# Ctrl-CAN.net
KiCad netlist of a schematic drawn in Altium Designer
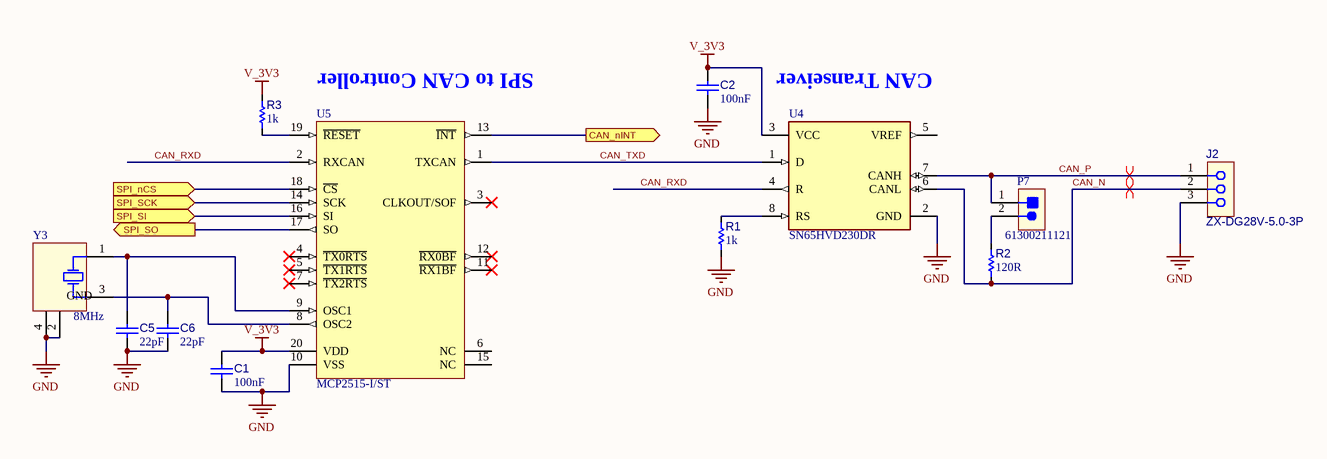
[diagram p0: Ctrl-CAN.SchDoc]

(export (version "E")
  (design (tool "Eeschema 10.0.6"))
  (components
    (comp (ref "C1")
      (value "100nF")
      (footprint "C_1005[0402]")
      (description "Capacitor type 1")
      (fields (field (name "TOLERANCE") "10%") (field (name "Comment") "CAP CER 100nF 50V 0402"))
      (libsource (lib "TEP-AltiumLib-Passives-RLC") (part "capacitor"))
    )
    (comp (ref "C2")
      (value "100nF")
      (footprint "C_1005[0402]")
      (description "Capacitor type 1")
      (fields (field (name "TOLERANCE") "10%") (field (name "Comment") "CAP CER 100nF 50V 0402"))
      (libsource (lib "TEP-AltiumLib-Passives-RLC") (part "capacitor"))
    )
    (comp (ref "C5")
      (value "22pF")
      (footprint "C_1005[0402]")
      (description "Capacitor type 1")
      (fields (field (name "TOLERANCE") "5%") (field (name "Comment") "CAP CER 22pF 50V COG 0402"))
      (libsource (lib "TEP-AltiumLib-Passives-RLC") (part "capacitor"))
    )
    (comp (ref "C6")
      (value "22pF")
      (footprint "C_1005[0402]")
      (description "Capacitor type 1")
      (fields (field (name "TOLERANCE") "5%") (field (name "Comment") "CAP CER 22pF 50V COG 0402"))
      (libsource (lib "TEP-AltiumLib-Passives-RLC") (part "capacitor"))
    )
    (comp (ref "J2")
      (value "ZX-DG28V-5.0-3P")
      (footprint "CONN_TERM_BLOCK_3POS_5mm_Model1")
      (description "CONN TERM BLOCK 3POS 5mm pitch")
      (libsource (lib "TEP-AltiumLib-Connectors") (part "CONN-5MM-3POS-TERM-BLOCK"))
    )
    (comp (ref "P7")
      (value "61300211121")
      (footprint "CONN_HDR_2POS_100MILS_TH")
      (description "CONN HEADER 2POS 100MIL")
      (libsource (lib "TEP-AltiumLib-Connectors") (part "CONN-100MIL-HDR-01X02"))
    )
    (comp (ref "R1")
      (value "1k")
      (footprint "R_1005[0402]")
      (description "Resistor type 1")
      (fields (field (name "TOLERANCE") "1%") (field (name "Comment") "Res 1k 1% 0402"))
      (libsource (lib "TEP-AltiumLib-Passives-RLC") (part "resistor"))
    )
    (comp (ref "R2")
      (value "120R")
      (footprint "R_3216[1206]")
      (description "Resistor type 1")
      (fields (field (name "TOLERANCE") "1%") (field (name "Comment") "Res 120R 1% 1206"))
      (libsource (lib "TEP-AltiumLib-Passives-RLC") (part "resistor"))
    )
    (comp (ref "R3")
      (value "1k")
      (footprint "R_1005[0402]")
      (description "Resistor type 1")
      (fields (field (name "TOLERANCE") "1%") (field (name "Comment") "Res 1k 1% 0402"))
      (libsource (lib "TEP-AltiumLib-Passives-RLC") (part "resistor"))
    )
    (comp (ref "U4")
      (value "SN65HVD230DR")
      (footprint "FP-D0008A-IPC_A")
      (description "IC TRANSCEIVER HALF 1/1 8SOIC")
      (libsource (lib "Altium Content Vault") (part "43b56812b1adf0e60a7acfb7c27ab91"))
    )
    (comp (ref "U5")
      (value "MCP2515-I/ST")
      (footprint "TSSOP-ST20_N")
      (description "Stand-Alone CAN Controller With SPI Interface, 20-Pin TSSOP, Industrial Temperature")
      (libsource (lib "Altium Content Vault") (part "COM-CAN-MCP2515-20"))
    )
    (comp (ref "Y3")
      (value "8MHz")
      (footprint "Y_32x25SMD4")
      (description "Crystal, 8MHz, 3.2 x 2.5 x 0.9 mm SMD")
      (fields (field (name "Comment") "XC32M4-8.000-F18LJDT"))
      (libsource (lib "SAP") (part "Y_XTAL25MHz"))
    )
  )
  (nets
    (net (code "1") (name "/CAN_N") (class "Default")
      (node (ref "J2") (pin "2") (pinfunction "2_2") (pintype "passive"))
      (node (ref "R2") (pin "1") (pinfunction "1_1") (pintype "passive"))
      (node (ref "U4") (pin "6") (pinfunction "CANL_6") (pintype "bidirectional"))
    )
    (net (code "2") (name "/CAN_P") (class "Default")
      (node (ref "J2") (pin "1") (pinfunction "1_1") (pintype "passive"))
      (node (ref "P7") (pin "1") (pinfunction "1_1") (pintype "passive"))
      (node (ref "U4") (pin "7") (pinfunction "CANH_7") (pintype "bidirectional"))
    )
    (net (code "3") (name "/CAN_RXD") (class "Default")
      (node (ref "U4") (pin "4") (pinfunction "R_4") (pintype "output"))
      (node (ref "U5") (pin "2") (pinfunction "RXCAN_2") (pintype "input"))
    )
    (net (code "4") (name "/CAN_TXD") (class "Default")
      (node (ref "U4") (pin "1") (pinfunction "D_1") (pintype "input"))
      (node (ref "U5") (pin "1") (pinfunction "TXCAN_1") (pintype "output"))
    )
    (net (code "5") (name "/CAN_nINT") (class "Default")
      (node (ref "U5") (pin "13") (pinfunction "~{INT}_13") (pintype "output"))
    )
    (net (code "6") (name "/SPI_SCK") (class "Default")
      (node (ref "U5") (pin "14") (pinfunction "SCK_14") (pintype "input"))
    )
    (net (code "7") (name "/SPI_SI") (class "Default")
      (node (ref "U5") (pin "16") (pinfunction "SI_16") (pintype "input"))
    )
    (net (code "8") (name "/SPI_SO") (class "Default")
      (node (ref "U5") (pin "17") (pinfunction "SO_17") (pintype "output"))
    )
    (net (code "9") (name "/SPI_nCS") (class "Default")
      (node (ref "U5") (pin "18") (pinfunction "~{CS}_18") (pintype "input"))
    )
    (net (code "10") (name "GND") (class "Default")
      (node (ref "C1") (pin "1") (pinfunction "1_1") (pintype "passive"))
      (node (ref "C2") (pin "1") (pinfunction "1_1") (pintype "passive"))
      (node (ref "C5") (pin "1") (pinfunction "1_1") (pintype "passive"))
      (node (ref "C6") (pin "1") (pinfunction "1_1") (pintype "passive"))
      (node (ref "J2") (pin "3") (pinfunction "3_3") (pintype "passive"))
      (node (ref "R1") (pin "1") (pinfunction "1_1") (pintype "passive"))
      (node (ref "U4") (pin "2") (pinfunction "GND_2") (pintype "power_in"))
      (node (ref "U5") (pin "10") (pinfunction "VSS_10") (pintype "power_in"))
      (node (ref "Y3") (pin "2") (pinfunction "GND_2") (pintype "power_in"))
      (node (ref "Y3") (pin "4") (pinfunction "GND_4") (pintype "power_in"))
    )
    (net (code "11") (name "Net-(P7-Pad2)") (class "Default")
      (node (ref "P7") (pin "2") (pinfunction "2_2") (pintype "passive"))
      (node (ref "R2") (pin "2") (pinfunction "2_2") (pintype "passive"))
    )
    (net (code "12") (name "Net-(U4-RS)") (class "Default")
      (node (ref "R1") (pin "2") (pinfunction "2_2") (pintype "passive"))
      (node (ref "U4") (pin "8") (pinfunction "RS_8") (pintype "input"))
    )
    (net (code "13") (name "Net-(U5-OSC1)") (class "Default")
      (node (ref "C5") (pin "2") (pinfunction "2_2") (pintype "passive"))
      (node (ref "U5") (pin "9") (pinfunction "OSC1_9") (pintype "input"))
      (node (ref "Y3") (pin "1") (pinfunction "XTAL_1") (pintype "passive"))
    )
    (net (code "14") (name "Net-(U5-OSC2)") (class "Default")
      (node (ref "C6") (pin "2") (pinfunction "2_2") (pintype "passive"))
      (node (ref "U5") (pin "8") (pinfunction "OSC2_8") (pintype "output"))
      (node (ref "Y3") (pin "3") (pinfunction "XTAL_3") (pintype "passive"))
    )
    (net (code "15") (name "Net-(U5-~{RESET})") (class "Default")
      (node (ref "R3") (pin "1") (pinfunction "1_1") (pintype "passive"))
      (node (ref "U5") (pin "19") (pinfunction "~{RESET}_19") (pintype "input"))
    )
    (net (code "16") (name "V_3V3") (class "Default")
      (node (ref "C1") (pin "2") (pinfunction "2_2") (pintype "passive"))
      (node (ref "C2") (pin "2") (pinfunction "2_2") (pintype "passive"))
      (node (ref "R3") (pin "2") (pinfunction "2_2") (pintype "passive"))
      (node (ref "U4") (pin "3") (pinfunction "VCC_3") (pintype "power_in"))
      (node (ref "U5") (pin "20") (pinfunction "VDD_20") (pintype "power_in"))
    )
    (net (code "17") (name "unconnected-(U4-VREF-Pad5)") (class "Default")
      (node (ref "U4") (pin "5") (pinfunction "VREF_5") (pintype "output"))
    )
    (net (code "18") (name "unconnected-(U5-CLKOUT{slash}SOF-Pad3)") (class "Default")
      (node (ref "U5") (pin "3") (pinfunction "CLKOUT/SOF_3") (pintype "output+no_connect"))
    )
    (net (code "19") (name "unconnected-(U5-NC-Pad6)") (class "Default")
      (node (ref "U5") (pin "6") (pinfunction "NC_6") (pintype "passive"))
    )
    (net (code "20") (name "unconnected-(U5-NC-Pad15)") (class "Default")
      (node (ref "U5") (pin "15") (pinfunction "NC_15") (pintype "passive"))
    )
    (net (code "21") (name "unconnected-(U5-~{RX0BF}-Pad12)") (class "Default")
      (node (ref "U5") (pin "12") (pinfunction "~{RX0BF}_12") (pintype "output+no_connect"))
    )
    (net (code "22") (name "unconnected-(U5-~{RX1BF}-Pad11)") (class "Default")
      (node (ref "U5") (pin "11") (pinfunction "~{RX1BF}_11") (pintype "output+no_connect"))
    )
    (net (code "23") (name "unconnected-(U5-~{TX0RTS}-Pad4)") (class "Default")
      (node (ref "U5") (pin "4") (pinfunction "~{TX0RTS}_4") (pintype "input+no_connect"))
    )
    (net (code "24") (name "unconnected-(U5-~{TX1RTS}-Pad5)") (class "Default")
      (node (ref "U5") (pin "5") (pinfunction "~{TX1RTS}_5") (pintype "input+no_connect"))
    )
    (net (code "25") (name "unconnected-(U5-~{TX2RTS}-Pad7)") (class "Default")
      (node (ref "U5") (pin "7") (pinfunction "~{TX2RTS}_7") (pintype "input+no_connect"))
    )
  )
)
